# PX4FMUv2_4_6_3.net
KiCad netlist of a schematic drawn in Altium Designer
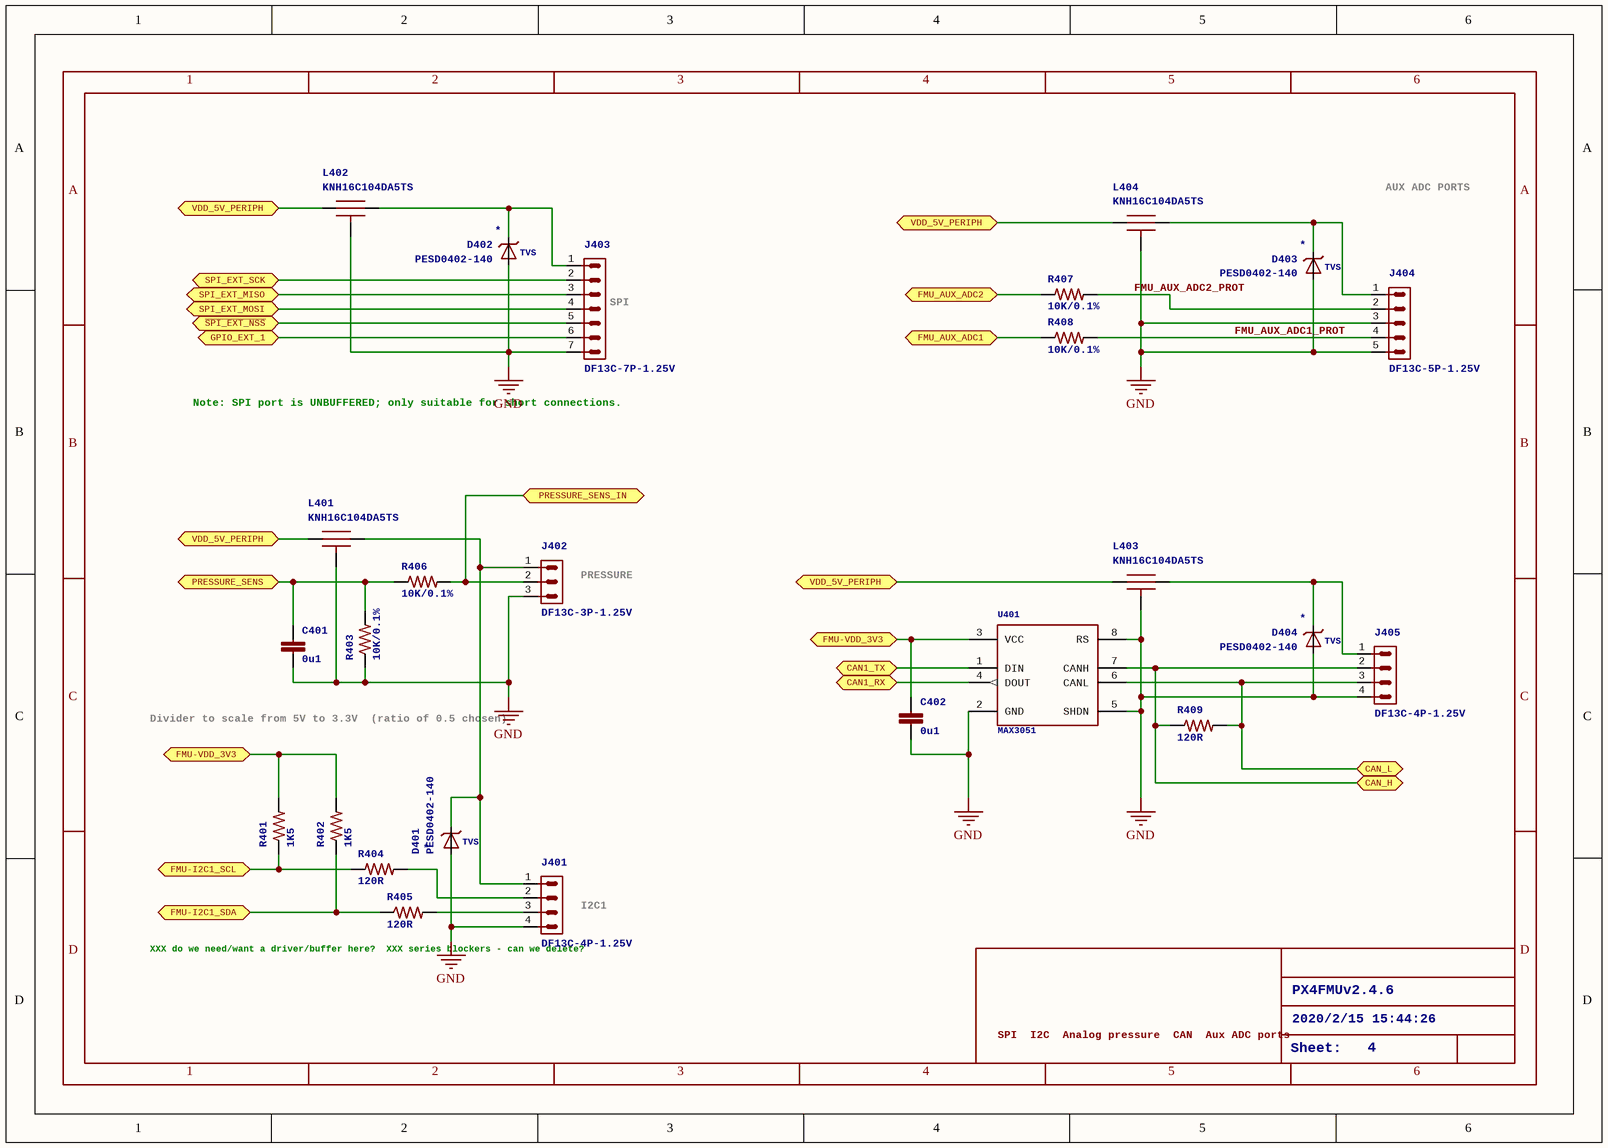
[diagram p0: PX4FMUv2.4.6_3.SchDoc]

(export (version "E")
  (design (tool "Eeschema 10.0.6"))
  (components
    (comp (ref "C401")
      (value "0u1")
      (footprint "0402-CAP")
      (description "CapacitorStandard 0603 ceramic capacitor, and 0.1\" leaded capacitor.")
      (fields (field (name "PARTNO") "CC0402ZRY5V7BB104"))
      (libsource (lib "pixhawk2") (part "CAP0402"))
    )
    (comp (ref "C402")
      (value "0u1")
      (footprint "0402-CAP")
      (description "CapacitorStandard 0603 ceramic capacitor, and 0.1\" leaded capacitor.")
      (fields (field (name "PARTNO") "CC0402ZRY5V7BB104"))
      (libsource (lib "pixhawk2") (part "CAP0402"))
    )
    (comp (ref "D401")
      (value "PESD0402-140")
      (footprint "0402-TVS")
      (fields (field (name "NAME") "*") (field (name "TVS") "TVS"))
      (libsource (lib "pixhawk2") (part "DIODE-TVS"))
    )
    (comp (ref "D402")
      (value "PESD0402-140")
      (footprint "0402-TVS")
      (fields (field (name "NAME") "*") (field (name "TVS") "TVS"))
      (libsource (lib "pixhawk2") (part "DIODE-TVS"))
    )
    (comp (ref "D403")
      (value "PESD0402-140")
      (footprint "0402-TVS")
      (fields (field (name "NAME") "*") (field (name "TVS") "TVS"))
      (libsource (lib "pixhawk2") (part "DIODE-TVS"))
    )
    (comp (ref "D404")
      (value "PESD0402-140")
      (footprint "0402-TVS")
      (fields (field (name "NAME") "*") (field (name "TVS") "TVS"))
      (libsource (lib "pixhawk2") (part "DIODE-TVS"))
    )
    (comp (ref "J401")
      (value "DF13C-4P-1.25V")
      (footprint "DF13C-4P-1.25V")
      (description "DF13-4P 1.25mm Pitch Miniature Crimping Connector.")
      (fields (field (name "PARTNO") "DF13C-4P-1.25V(20)") (field (name "LIBRARYNAME") "con-hirose-df13"))
      (libsource (lib "con-hirose-df13") (part "DF13-4P-1.25V"))
    )
    (comp (ref "J402")
      (value "DF13C-3P-1.25V")
      (footprint "DF13C-3P-1.25V")
      (description "DF13-3P 1.25mm Pitch Miniature Crimping Connector.")
      (fields (field (name "PARTNO") "DF13C-3P-1.25V(20)") (field (name "LIBRARYNAME") "con-hirose-df13"))
      (libsource (lib "con-hirose-df13") (part "DF13-3P-1.25V"))
    )
    (comp (ref "J403")
      (value "DF13C-7P-1.25V")
      (footprint "DF13C-7P-1.25V")
      (description "DF13-7P 1.25mm Pitch Miniature Crimping Connector.")
      (fields (field (name "PARTNO") "DF13C-7P-1.25V(20)") (field (name "LIBRARYNAME") "con-hirose-df13"))
      (libsource (lib "con-hirose-df13") (part "DF13-7P-1.25V"))
    )
    (comp (ref "J404")
      (value "DF13C-5P-1.25V")
      (footprint "DF13C-5P-1.25V")
      (description "DF13-5P 1.25mm Pitch Miniature Crimping Connector.")
      (fields (field (name "PARTNO") "DF13C-5P-1.25V(20)") (field (name "LIBRARYNAME") "con-hirose-df13"))
      (libsource (lib "con-hirose-df13") (part "DF13-5P-1.25V"))
    )
    (comp (ref "J405")
      (value "DF13C-4P-1.25V")
      (footprint "DF13C-4P-1.25V")
      (description "DF13-4P 1.25mm Pitch Miniature Crimping Connector.")
      (fields (field (name "PARTNO") "DF13C-4P-1.25V(20)") (field (name "LIBRARYNAME") "con-hirose-df13"))
      (libsource (lib "con-hirose-df13") (part "DF13-4P-1.25V"))
    )
    (comp (ref "L401")
      (value "KNH16C104DA5TS")
      (footprint "KYOCERA-KNH16-DA")
      (description "Kyocera KNH16C104DA5TS EMI filter")
      (libsource (lib "pixhawk2") (part "KNH16C104DA5TS"))
    )
    (comp (ref "L402")
      (value "KNH16C104DA5TS")
      (footprint "KYOCERA-KNH16-DA")
      (description "Kyocera KNH16C104DA5TS EMI filter")
      (libsource (lib "pixhawk2") (part "KNH16C104DA5TS"))
    )
    (comp (ref "L403")
      (value "KNH16C104DA5TS")
      (footprint "KYOCERA-KNH16-DA")
      (description "Kyocera KNH16C104DA5TS EMI filter")
      (libsource (lib "pixhawk2") (part "KNH16C104DA5TS"))
    )
    (comp (ref "L404")
      (value "KNH16C104DA5TS")
      (footprint "KYOCERA-KNH16-DA")
      (description "Kyocera KNH16C104DA5TS EMI filter")
      (libsource (lib "pixhawk2") (part "KNH16C104DA5TS"))
    )
    (comp (ref "R401")
      (value "1K5")
      (footprint "0402-RES")
      (fields (field (name "PARTNO") "RC0402FR-071K5L"))
      (libsource (lib "pixhawk2") (part "RESISTOR0402-RES"))
    )
    (comp (ref "R402")
      (value "1K5")
      (footprint "0402-RES")
      (fields (field (name "PARTNO") "RC0402FR-071K5L"))
      (libsource (lib "pixhawk2") (part "RESISTOR0402-RES"))
    )
    (comp (ref "R403")
      (value "10K/0.1%")
      (footprint "0402-RES")
      (fields (field (name "PARTNO") "ERA-2AEB103X"))
      (libsource (lib "pixhawk2") (part "RESISTOR0402-RES"))
    )
    (comp (ref "R404")
      (value "120R")
      (footprint "0402-RES")
      (fields (field (name "PARTNO") "RC0402FR-07120RL"))
      (libsource (lib "pixhawk2") (part "RESISTOR0402-RES"))
    )
    (comp (ref "R405")
      (value "120R")
      (footprint "0402-RES")
      (fields (field (name "PARTNO") "RC0402FR-07120RL"))
      (libsource (lib "pixhawk2") (part "RESISTOR0402-RES"))
    )
    (comp (ref "R406")
      (value "10K/0.1%")
      (footprint "0402-RES")
      (fields (field (name "PARTNO") "ERA-2AEB103X"))
      (libsource (lib "pixhawk2") (part "RESISTOR0402-RES"))
    )
    (comp (ref "R407")
      (value "10K/0.1%")
      (footprint "0402-RES")
      (fields (field (name "PARTNO") "ERA-2AEB103X"))
      (libsource (lib "pixhawk2") (part "RESISTOR0402-RES"))
    )
    (comp (ref "R408")
      (value "10K/0.1%")
      (footprint "0402-RES")
      (fields (field (name "PARTNO") "ERA-2AEB103X"))
      (libsource (lib "pixhawk2") (part "RESISTOR0402-RES"))
    )
    (comp (ref "R409")
      (value "120R")
      (footprint "0402-RES")
      (fields (field (name "PARTNO") "RC0402FR-07120RL"))
      (libsource (lib "pixhawk2") (part "RESISTOR0402-RES"))
    )
    (comp (ref "U401")
      (value "MAX3051")
      (footprint "SOT23-8")
      (description "3.3-V CAN TRANSCEIVER")
      (fields (field (name "PARTNO") "MAX3051EKA"))
      (libsource (lib "pixhawk2") (part "MAX3051MAX3051EKA"))
    )
  )
  (nets
    (net (code "1") (name "/CAN1_RX") (class "Default")
      (node (ref "U401") (pin "4") (pinfunction "DOUT_4") (pintype "output"))
    )
    (net (code "2") (name "/CAN1_TX") (class "Default")
      (node (ref "U401") (pin "1") (pinfunction "DIN_1") (pintype "passive"))
    )
    (net (code "3") (name "/CAN_H") (class "Default")
      (node (ref "J405") (pin "2") (pinfunction "2_2") (pintype "passive"))
      (node (ref "R409") (pin "P$1") (pinfunction "1_P$1") (pintype "passive"))
      (node (ref "U401") (pin "7") (pinfunction "CANH_7") (pintype "passive"))
    )
    (net (code "4") (name "/CAN_L") (class "Default")
      (node (ref "J405") (pin "3") (pinfunction "3_3") (pintype "passive"))
      (node (ref "R409") (pin "P$2") (pinfunction "2_P$2") (pintype "passive"))
      (node (ref "U401") (pin "6") (pinfunction "CANL_6") (pintype "passive"))
    )
    (net (code "5") (name "/FMU-I2C1_SCL") (class "Default")
      (node (ref "R401") (pin "P$1") (pinfunction "1_P$1") (pintype "passive"))
      (node (ref "R404") (pin "P$1") (pinfunction "1_P$1") (pintype "passive"))
    )
    (net (code "6") (name "/FMU-I2C1_SDA") (class "Default")
      (node (ref "R402") (pin "P$1") (pinfunction "1_P$1") (pintype "passive"))
      (node (ref "R405") (pin "P$1") (pinfunction "1_P$1") (pintype "passive"))
    )
    (net (code "7") (name "/FMU-VDD_3V3") (class "Default")
      (node (ref "C402") (pin "P$1") (pinfunction "1_P$1") (pintype "passive"))
      (node (ref "R401") (pin "P$2") (pinfunction "2_P$2") (pintype "passive"))
      (node (ref "R402") (pin "P$2") (pinfunction "2_P$2") (pintype "passive"))
      (node (ref "U401") (pin "3") (pinfunction "VCC_3") (pintype "passive"))
    )
    (net (code "8") (name "/FMU_AUX_ADC1") (class "Default")
      (node (ref "R408") (pin "P$1") (pinfunction "1_P$1") (pintype "passive"))
    )
    (net (code "9") (name "/FMU_AUX_ADC1_PROT") (class "Default")
      (node (ref "J404") (pin "4") (pinfunction "4_4") (pintype "passive"))
      (node (ref "R408") (pin "P$2") (pinfunction "2_P$2") (pintype "passive"))
    )
    (net (code "10") (name "/FMU_AUX_ADC2") (class "Default")
      (node (ref "R407") (pin "P$1") (pinfunction "1_P$1") (pintype "passive"))
    )
    (net (code "11") (name "/FMU_AUX_ADC2_PROT") (class "Default")
      (node (ref "J404") (pin "2") (pinfunction "2_2") (pintype "passive"))
      (node (ref "R407") (pin "P$2") (pinfunction "2_P$2") (pintype "passive"))
    )
    (net (code "12") (name "/GPIO_EXT_1") (class "Default")
      (node (ref "J403") (pin "6") (pinfunction "6_6") (pintype "passive"))
    )
    (net (code "13") (name "/PRESSURE_SENS") (class "Default")
      (node (ref "C401") (pin "P$1") (pinfunction "1_P$1") (pintype "passive"))
      (node (ref "R403") (pin "P$2") (pinfunction "2_P$2") (pintype "passive"))
      (node (ref "R406") (pin "P$1") (pinfunction "1_P$1") (pintype "passive"))
    )
    (net (code "14") (name "/PRESSURE_SENS_IN") (class "Default")
      (node (ref "J402") (pin "2") (pinfunction "2_2") (pintype "passive"))
      (node (ref "R406") (pin "P$2") (pinfunction "2_P$2") (pintype "passive"))
    )
    (net (code "15") (name "/SPI_EXT_MISO") (class "Default")
      (node (ref "J403") (pin "3") (pinfunction "3_3") (pintype "passive"))
    )
    (net (code "16") (name "/SPI_EXT_MOSI") (class "Default")
      (node (ref "J403") (pin "4") (pinfunction "4_4") (pintype "passive"))
    )
    (net (code "17") (name "/SPI_EXT_SCK") (class "Default")
      (node (ref "J403") (pin "2") (pinfunction "2_2") (pintype "passive"))
    )
    (net (code "18") (name "/VDD_5V_PERIPH") (class "Default")
      (node (ref "L401") (pin "P$1") (pinfunction "P$1_P$1") (pintype "passive"))
      (node (ref "L402") (pin "P$1") (pinfunction "P$1_P$1") (pintype "passive"))
      (node (ref "L403") (pin "P$1") (pinfunction "P$1_P$1") (pintype "passive"))
      (node (ref "L404") (pin "P$1") (pinfunction "P$1_P$1") (pintype "passive"))
    )
    (net (code "19") (name "/~{SPI_EXT_NSS}") (class "Default")
      (node (ref "J403") (pin "5") (pinfunction "5_5") (pintype "passive"))
    )
    (net (code "20") (name "GND") (class "Default")
      (node (ref "C401") (pin "P$2") (pinfunction "2_P$2") (pintype "passive"))
      (node (ref "C402") (pin "P$2") (pinfunction "2_P$2") (pintype "passive"))
      (node (ref "D401") (pin "A") (pinfunction "A_A") (pintype "passive"))
      (node (ref "D402") (pin "A") (pinfunction "A_A") (pintype "passive"))
      (node (ref "D403") (pin "A") (pinfunction "A_A") (pintype "passive"))
      (node (ref "D404") (pin "A") (pinfunction "A_A") (pintype "passive"))
      (node (ref "J401") (pin "4") (pinfunction "4_4") (pintype "passive"))
      (node (ref "J402") (pin "3") (pinfunction "3_3") (pintype "passive"))
      (node (ref "J403") (pin "7") (pinfunction "7_7") (pintype "passive"))
      (node (ref "J404") (pin "3") (pinfunction "3_3") (pintype "passive"))
      (node (ref "J404") (pin "5") (pinfunction "5_5") (pintype "passive"))
      (node (ref "J405") (pin "4") (pinfunction "4_4") (pintype "passive"))
      (node (ref "L401") (pin "P$3_P$4_P$5") (pinfunction "P$3_P$3_P$4_P$5") (pintype "passive"))
      (node (ref "L402") (pin "P$3_P$4_P$5") (pinfunction "P$3_P$3_P$4_P$5") (pintype "passive"))
      (node (ref "L403") (pin "P$3_P$4_P$5") (pinfunction "P$3_P$3_P$4_P$5") (pintype "passive"))
      (node (ref "L404") (pin "P$3_P$4_P$5") (pinfunction "P$3_P$3_P$4_P$5") (pintype "passive"))
      (node (ref "R403") (pin "P$1") (pinfunction "1_P$1") (pintype "passive"))
      (node (ref "U401") (pin "2") (pinfunction "GND_2") (pintype "open_emitter"))
      (node (ref "U401") (pin "5") (pinfunction "SHDN_5") (pintype "passive"))
      (node (ref "U401") (pin "8") (pinfunction "RS_8") (pintype "passive"))
    )
    (net (code "21") (name "Net-(D401-PadC)") (class "Default")
      (node (ref "D401") (pin "C") (pinfunction "C_C") (pintype "passive"))
      (node (ref "J401") (pin "1") (pinfunction "1_1") (pintype "passive"))
      (node (ref "J402") (pin "1") (pinfunction "1_1") (pintype "passive"))
      (node (ref "L401") (pin "P$2") (pinfunction "P$2_P$2") (pintype "passive"))
    )
    (net (code "22") (name "Net-(D402-PadC)") (class "Default")
      (node (ref "D402") (pin "C") (pinfunction "C_C") (pintype "passive"))
      (node (ref "J403") (pin "1") (pinfunction "1_1") (pintype "passive"))
      (node (ref "L402") (pin "P$2") (pinfunction "P$2_P$2") (pintype "passive"))
    )
    (net (code "23") (name "Net-(D403-PadC)") (class "Default")
      (node (ref "D403") (pin "C") (pinfunction "C_C") (pintype "passive"))
      (node (ref "J404") (pin "1") (pinfunction "1_1") (pintype "passive"))
      (node (ref "L404") (pin "P$2") (pinfunction "P$2_P$2") (pintype "passive"))
    )
    (net (code "24") (name "Net-(D404-PadC)") (class "Default")
      (node (ref "D404") (pin "C") (pinfunction "C_C") (pintype "passive"))
      (node (ref "J405") (pin "1") (pinfunction "1_1") (pintype "passive"))
      (node (ref "L403") (pin "P$2") (pinfunction "P$2_P$2") (pintype "passive"))
    )
    (net (code "25") (name "Net-(R404-2)") (class "Default")
      (node (ref "J401") (pin "2") (pinfunction "2_2") (pintype "passive"))
      (node (ref "R404") (pin "P$2") (pinfunction "2_P$2") (pintype "passive"))
    )
    (net (code "26") (name "Net-(R405-2)") (class "Default")
      (node (ref "J401") (pin "3") (pinfunction "3_3") (pintype "passive"))
      (node (ref "R405") (pin "P$2") (pinfunction "2_P$2") (pintype "passive"))
    )
  )
)
